# SCH_MCU-IR_Temp-Control-Relay_2025-03-15.net
KiCad netlist of a schematic drawn in EasyEDA
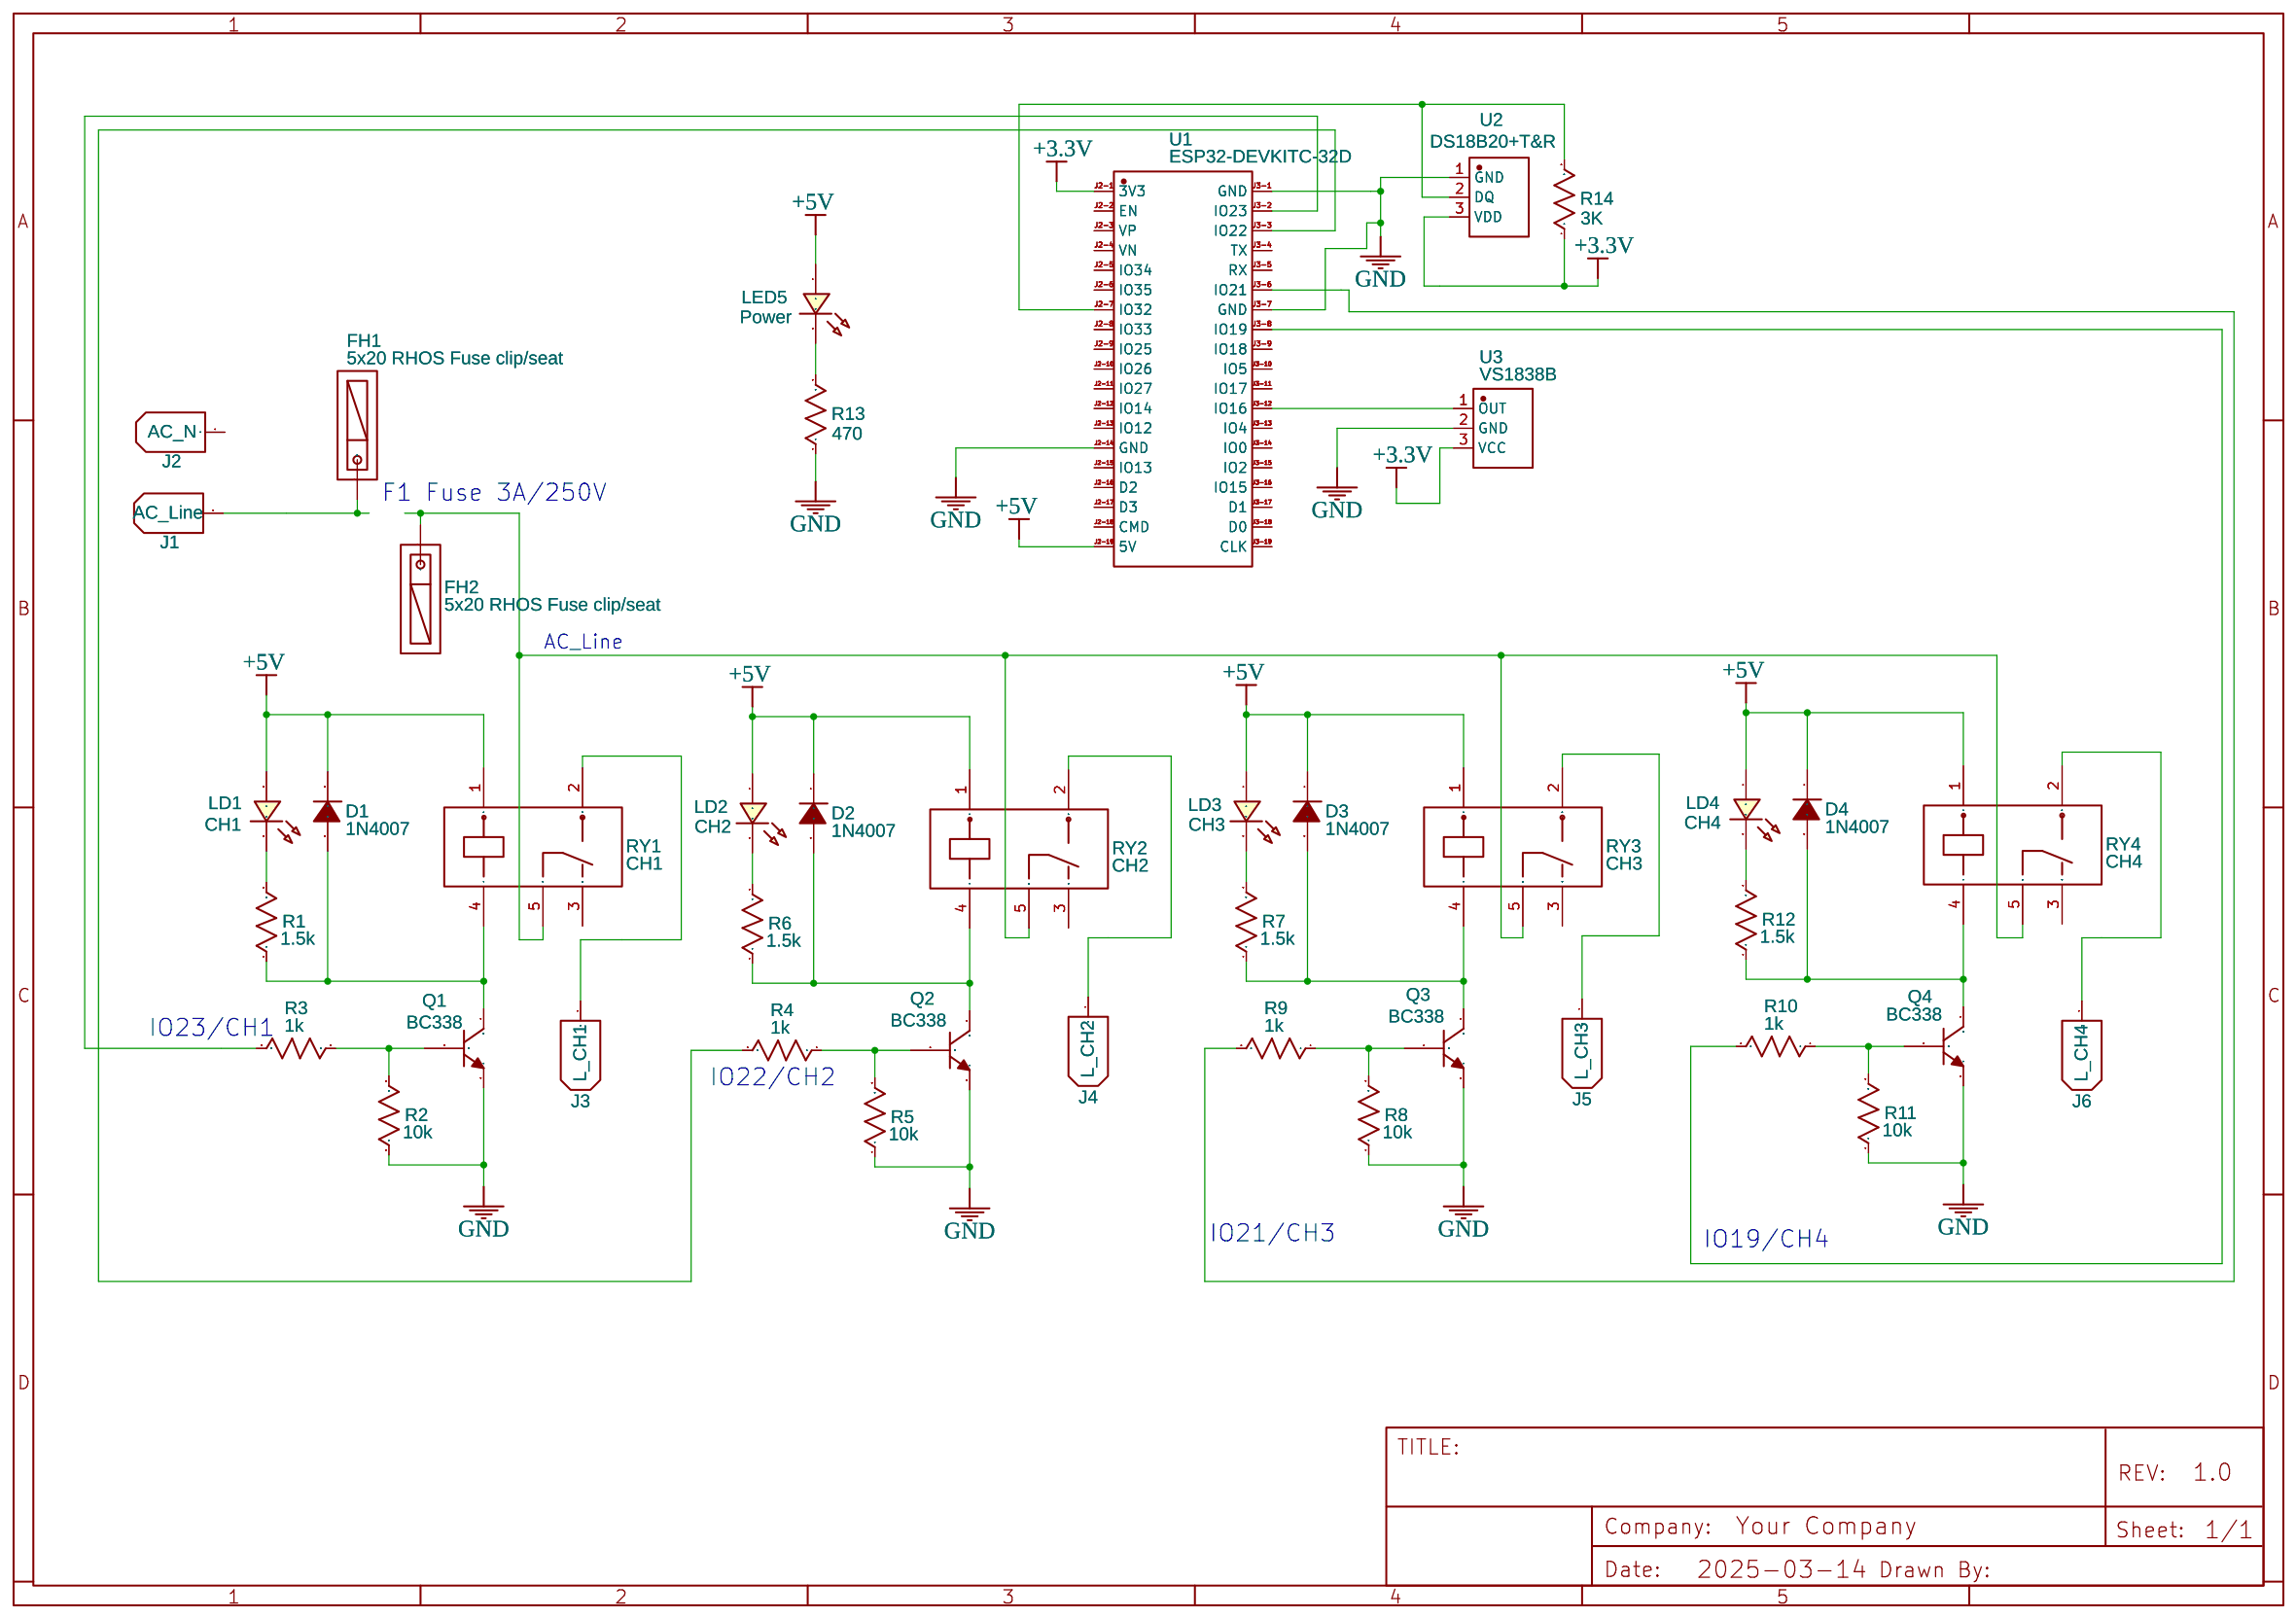
[diagram p0: schematic sheet]

(export (version "E")
  (design (tool "Eeschema 10.0.6"))
  (components
    (comp (ref "D1")
      (value "1N4007")
      (fields (field (name "Manufacturer") "ST(先科)"))
      (libsource (lib "") (part "1N4007"))
    )
    (comp (ref "D2")
      (value "1N4007")
      (fields (field (name "Manufacturer") "ST(先科)"))
      (libsource (lib "") (part "1N4007"))
    )
    (comp (ref "D3")
      (value "1N4007")
      (fields (field (name "Manufacturer") "ST(先科)"))
      (libsource (lib "") (part "1N4007"))
    )
    (comp (ref "D4")
      (value "1N4007")
      (fields (field (name "Manufacturer") "ST(先科)"))
      (libsource (lib "") (part "1N4007"))
    )
    (comp (ref "FH1")
      (value "5x20 RHOS Fuse clip/seat")
      (fields (field (name "Manufacturer Part") "5x20 环保 保险管夹/座") (field (name "Manufacturer") "xcfuse(旭程)"))
      (libsource (lib "") (part "5x20 RHOS Fuse clip/seat"))
    )
    (comp (ref "FH2")
      (value "5x20 RHOS Fuse clip/seat")
      (fields (field (name "Manufacturer Part") "5x20 环保 保险管夹/座") (field (name "Manufacturer") "xcfuse(旭程)"))
      (libsource (lib "") (part "5x20 RHOS Fuse clip/seat_1"))
    )
    (comp (ref "J1")
      (value "AC_Line")
      (fields
        (field (name "Manufacturer Part") "63849-1")
        (field (name "Manufacturer") "TE Connectivity(美国泰科)")
      )
      (libsource (lib "") (part "63849-1_1"))
    )
    (comp (ref "J2")
      (value "AC_N")
      (fields
        (field (name "Manufacturer Part") "63849-1")
        (field (name "Manufacturer") "TE Connectivity(美国泰科)")
      )
      (libsource (lib "") (part "63849-1_1"))
    )
    (comp (ref "J3")
      (value "L_CH1")
      (fields
        (field (name "Manufacturer Part") "63849-1")
        (field (name "Manufacturer") "TE Connectivity(美国泰科)")
      )
      (libsource (lib "") (part "63849-1"))
    )
    (comp (ref "J4")
      (value "L_CH2")
      (fields
        (field (name "Manufacturer Part") "63849-1")
        (field (name "Manufacturer") "TE Connectivity(美国泰科)")
      )
      (libsource (lib "") (part "63849-1"))
    )
    (comp (ref "J5")
      (value "L_CH3")
      (fields
        (field (name "Manufacturer Part") "63849-1")
        (field (name "Manufacturer") "TE Connectivity(美国泰科)")
      )
      (libsource (lib "") (part "63849-1"))
    )
    (comp (ref "J6")
      (value "L_CH4")
      (fields
        (field (name "Manufacturer Part") "63849-1")
        (field (name "Manufacturer") "TE Connectivity(美国泰科)")
      )
      (libsource (lib "") (part "63849-1"))
    )
    (comp (ref "LD1")
      (value "CH1")
      (fields
        (field (name "Manufacturer Part") "204-10SDRD/S530-A3-L")
        (field (name "Manufacturer") "EVERLIGHT(台湾亿光)")
      )
      (libsource (lib "") (part "LED-TH-3mm_R"))
    )
    (comp (ref "LD2")
      (value "CH2")
      (fields
        (field (name "Manufacturer Part") "204-10SDRD/S530-A3-L")
        (field (name "Manufacturer") "EVERLIGHT(台湾亿光)")
      )
      (libsource (lib "") (part "LED-TH-3mm_R"))
    )
    (comp (ref "LD3")
      (value "CH3")
      (fields
        (field (name "Manufacturer Part") "204-10SDRD/S530-A3-L")
        (field (name "Manufacturer") "EVERLIGHT(台湾亿光)")
      )
      (libsource (lib "") (part "LED-TH-3mm_R"))
    )
    (comp (ref "LD4")
      (value "CH4")
      (fields
        (field (name "Manufacturer Part") "204-10SDRD/S530-A3-L")
        (field (name "Manufacturer") "EVERLIGHT(台湾亿光)")
      )
      (libsource (lib "") (part "LED-TH-3mm_R"))
    )
    (comp (ref "LED5")
      (value "Power")
      (fields
        (field (name "Manufacturer Part") "204-10SDRD/S530-A3-L")
        (field (name "Manufacturer") "EVERLIGHT(台湾亿光)")
      )
      (libsource (lib "") (part "LED-TH-3mm_R_1"))
    )
    (comp (ref "Q1")
      (value "BC338")
      (fields (field (name "Manufacturer Part") "BC547BTF") (field (name "Manufacturer") "onsemi(安森美)"))
      (libsource (lib "") (part "BC547BTF"))
    )
    (comp (ref "Q2")
      (value "BC338")
      (fields (field (name "Manufacturer Part") "BC547BTF") (field (name "Manufacturer") "onsemi(安森美)"))
      (libsource (lib "") (part "BC547BTF"))
    )
    (comp (ref "Q3")
      (value "BC338")
      (fields (field (name "Manufacturer Part") "BC547BTF") (field (name "Manufacturer") "onsemi(安森美)"))
      (libsource (lib "") (part "BC547BTF"))
    )
    (comp (ref "Q4")
      (value "BC338")
      (fields (field (name "Manufacturer Part") "BC547BTF") (field (name "Manufacturer") "onsemi(安森美)"))
      (libsource (lib "") (part "BC547BTF"))
    )
    (comp (ref "R1") (value "1.5k") (libsource (lib "") (part "R_AXIAL-0.3_US")))
    (comp (ref "R2") (value "10k") (libsource (lib "") (part "R_AXIAL-0.3_US")))
    (comp (ref "R3") (value "1k") (libsource (lib "") (part "R_AXIAL-0.3_US_1")))
    (comp (ref "R4") (value "1k") (libsource (lib "") (part "R_AXIAL-0.3_US_1")))
    (comp (ref "R5") (value "10k") (libsource (lib "") (part "R_AXIAL-0.3_US")))
    (comp (ref "R6") (value "1.5k") (libsource (lib "") (part "R_AXIAL-0.3_US")))
    (comp (ref "R7") (value "1.5k") (libsource (lib "") (part "R_AXIAL-0.3_US")))
    (comp (ref "R8") (value "10k") (libsource (lib "") (part "R_AXIAL-0.3_US")))
    (comp (ref "R9") (value "1k") (libsource (lib "") (part "R_AXIAL-0.3_US_1")))
    (comp (ref "R10") (value "1k") (libsource (lib "") (part "R_AXIAL-0.3_US_1")))
    (comp (ref "R11") (value "10k") (libsource (lib "") (part "R_AXIAL-0.3_US")))
    (comp (ref "R12") (value "1.5k") (libsource (lib "") (part "R_AXIAL-0.3_US")))
    (comp (ref "R13") (value "470") (libsource (lib "") (part "R_AXIAL-0.3_US")))
    (comp (ref "R14") (value "3K") (libsource (lib "") (part "R_AXIAL-0.3_US")))
    (comp (ref "RY1")
      (value "CH1")
      (fields (field (name "Manufacturer Part") "SRD-12VDC-SL-C") (field (name "Manufacturer") "松乐"))
      (libsource (lib "") (part "SRD-12VDC-SL-C"))
    )
    (comp (ref "RY2")
      (value "CH2")
      (fields (field (name "Manufacturer Part") "SRD-12VDC-SL-C") (field (name "Manufacturer") "松乐"))
      (libsource (lib "") (part "SRD-12VDC-SL-C"))
    )
    (comp (ref "RY3")
      (value "CH3")
      (fields (field (name "Manufacturer Part") "SRD-12VDC-SL-C") (field (name "Manufacturer") "松乐"))
      (libsource (lib "") (part "SRD-12VDC-SL-C"))
    )
    (comp (ref "RY4")
      (value "CH4")
      (fields (field (name "Manufacturer Part") "SRD-12VDC-SL-C") (field (name "Manufacturer") "松乐"))
      (libsource (lib "") (part "SRD-12VDC-SL-C"))
    )
    (comp (ref "U1")
      (value "ESP32-DEVKITC-32D")
      (fields
        (field (name "Manufacturer Part") "ESP32-DevKitC-32D")
        (field (name "Manufacturer") "ESPRESSIF(乐鑫)")
      )
      (libsource (lib "") (part "ESP32-DEVKITC-32D"))
    )
    (comp (ref "U2")
      (value "DS18B20+T&R")
      (fields (field (name "Manufacturer") "ADI(亚德诺)/MAXIM(美信)"))
      (libsource (lib "") (part "DS18B20+T&amp;R"))
    )
    (comp (ref "U3") (value "VS1838B") (libsource (lib "") (part "VS1838B")))
  )
  (nets
    (net (code "1") (name "+3.3V") (class "Default")
      (node (ref "R14") (pin "1") (pinfunction "1_1") (pintype "unspecified"))
      (node (ref "U1") (pin "J2-1") (pinfunction "3V3_J2-1") (pintype "unspecified"))
      (node (ref "U2") (pin "3") (pinfunction "VDD_3") (pintype "unspecified"))
      (node (ref "U3") (pin "3") (pinfunction "VCC_3") (pintype "unspecified"))
    )
    (net (code "2") (name "+5V") (class "Default")
      (node (ref "D1") (pin "1") (pinfunction "K_1") (pintype "unspecified"))
      (node (ref "D2") (pin "1") (pinfunction "K_1") (pintype "unspecified"))
      (node (ref "D3") (pin "1") (pinfunction "K_1") (pintype "unspecified"))
      (node (ref "D4") (pin "1") (pinfunction "K_1") (pintype "unspecified"))
      (node (ref "LD1") (pin "1") (pinfunction "1_1") (pintype "unspecified"))
      (node (ref "LD2") (pin "1") (pinfunction "1_1") (pintype "unspecified"))
      (node (ref "LD3") (pin "1") (pinfunction "1_1") (pintype "unspecified"))
      (node (ref "LD4") (pin "1") (pinfunction "1_1") (pintype "unspecified"))
      (node (ref "LED5") (pin "1") (pinfunction "1_1") (pintype "unspecified"))
      (node (ref "RY1") (pin "1") (pinfunction "1_1") (pintype "input"))
      (node (ref "RY2") (pin "1") (pinfunction "1_1") (pintype "input"))
      (node (ref "RY3") (pin "1") (pinfunction "1_1") (pintype "input"))
      (node (ref "RY4") (pin "1") (pinfunction "1_1") (pintype "input"))
      (node (ref "U1") (pin "J2-19") (pinfunction "5V_J2-19") (pintype "unspecified"))
    )
    (net (code "3") (name "GND") (class "Default")
      (node (ref "Q1") (pin "3") (pinfunction "E_3") (pintype "unspecified"))
      (node (ref "Q2") (pin "3") (pinfunction "E_3") (pintype "unspecified"))
      (node (ref "Q3") (pin "3") (pinfunction "E_3") (pintype "unspecified"))
      (node (ref "Q4") (pin "3") (pinfunction "E_3") (pintype "unspecified"))
      (node (ref "R11") (pin "1") (pinfunction "1_1") (pintype "unspecified"))
      (node (ref "R13") (pin "1") (pinfunction "1_1") (pintype "unspecified"))
      (node (ref "R2") (pin "1") (pinfunction "1_1") (pintype "unspecified"))
      (node (ref "R5") (pin "1") (pinfunction "1_1") (pintype "unspecified"))
      (node (ref "R8") (pin "1") (pinfunction "1_1") (pintype "unspecified"))
      (node (ref "U1") (pin "J2-14") (pinfunction "GND_J2-14") (pintype "unspecified"))
      (node (ref "U1") (pin "J3-1") (pinfunction "GND_J3-1") (pintype "unspecified"))
      (node (ref "U1") (pin "J3-7") (pinfunction "GND_J3-7") (pintype "unspecified"))
      (node (ref "U2") (pin "1") (pinfunction "GND_1") (pintype "unspecified"))
      (node (ref "U3") (pin "2") (pinfunction "GND_2") (pintype "unspecified"))
    )
    (net (code "4") (name "Net-(D1-A)") (class "Default")
      (node (ref "D1") (pin "2") (pinfunction "A_2") (pintype "unspecified"))
      (node (ref "Q1") (pin "1") (pinfunction "C_1") (pintype "unspecified"))
      (node (ref "R1") (pin "1") (pinfunction "1_1") (pintype "unspecified"))
      (node (ref "RY1") (pin "4") (pinfunction "4_4") (pintype "input"))
    )
    (net (code "5") (name "Net-(D2-A)") (class "Default")
      (node (ref "D2") (pin "2") (pinfunction "A_2") (pintype "unspecified"))
      (node (ref "Q2") (pin "1") (pinfunction "C_1") (pintype "unspecified"))
      (node (ref "R6") (pin "1") (pinfunction "1_1") (pintype "unspecified"))
      (node (ref "RY2") (pin "4") (pinfunction "4_4") (pintype "input"))
    )
    (net (code "6") (name "Net-(D3-A)") (class "Default")
      (node (ref "D3") (pin "2") (pinfunction "A_2") (pintype "unspecified"))
      (node (ref "Q3") (pin "1") (pinfunction "C_1") (pintype "unspecified"))
      (node (ref "R7") (pin "1") (pinfunction "1_1") (pintype "unspecified"))
      (node (ref "RY3") (pin "4") (pinfunction "4_4") (pintype "input"))
    )
    (net (code "7") (name "Net-(D4-A)") (class "Default")
      (node (ref "D4") (pin "2") (pinfunction "A_2") (pintype "unspecified"))
      (node (ref "Q4") (pin "1") (pinfunction "C_1") (pintype "unspecified"))
      (node (ref "R12") (pin "1") (pinfunction "1_1") (pintype "unspecified"))
      (node (ref "RY4") (pin "4") (pinfunction "4_4") (pintype "input"))
    )
    (net (code "8") (name "Net-(FH1-Pad1)") (class "Default")
      (node (ref "FH1") (pin "1") (pinfunction "1_1") (pintype "unspecified"))
      (node (ref "J1") (pin "1") (pinfunction "1_1") (pintype "unspecified"))
    )
    (net (code "9") (name "Net-(FH2-Pad1)") (class "Default")
      (node (ref "FH2") (pin "1") (pinfunction "1_1") (pintype "unspecified"))
      (node (ref "RY1") (pin "5") (pinfunction "5_5") (pintype "input"))
      (node (ref "RY2") (pin "5") (pinfunction "5_5") (pintype "input"))
      (node (ref "RY3") (pin "5") (pinfunction "5_5") (pintype "input"))
      (node (ref "RY4") (pin "5") (pinfunction "5_5") (pintype "input"))
    )
    (net (code "10") (name "Net-(J3-Pad1)") (class "Default")
      (node (ref "J3") (pin "1") (pinfunction "1_1") (pintype "unspecified"))
      (node (ref "RY1") (pin "2") (pinfunction "2_2") (pintype "input"))
    )
    (net (code "11") (name "Net-(J4-Pad1)") (class "Default")
      (node (ref "J4") (pin "1") (pinfunction "1_1") (pintype "unspecified"))
      (node (ref "RY2") (pin "2") (pinfunction "2_2") (pintype "input"))
    )
    (net (code "12") (name "Net-(J5-Pad1)") (class "Default")
      (node (ref "J5") (pin "1") (pinfunction "1_1") (pintype "unspecified"))
      (node (ref "RY3") (pin "2") (pinfunction "2_2") (pintype "input"))
    )
    (net (code "13") (name "Net-(J6-Pad1)") (class "Default")
      (node (ref "J6") (pin "1") (pinfunction "1_1") (pintype "unspecified"))
      (node (ref "RY4") (pin "2") (pinfunction "2_2") (pintype "input"))
    )
    (net (code "14") (name "Net-(LD1-Pad2)") (class "Default")
      (node (ref "LD1") (pin "2") (pinfunction "2_2") (pintype "unspecified"))
      (node (ref "R1") (pin "2") (pinfunction "2_2") (pintype "unspecified"))
    )
    (net (code "15") (name "Net-(LD2-Pad2)") (class "Default")
      (node (ref "LD2") (pin "2") (pinfunction "2_2") (pintype "unspecified"))
      (node (ref "R6") (pin "2") (pinfunction "2_2") (pintype "unspecified"))
    )
    (net (code "16") (name "Net-(LD3-Pad2)") (class "Default")
      (node (ref "LD3") (pin "2") (pinfunction "2_2") (pintype "unspecified"))
      (node (ref "R7") (pin "2") (pinfunction "2_2") (pintype "unspecified"))
    )
    (net (code "17") (name "Net-(LD4-Pad2)") (class "Default")
      (node (ref "LD4") (pin "2") (pinfunction "2_2") (pintype "unspecified"))
      (node (ref "R12") (pin "2") (pinfunction "2_2") (pintype "unspecified"))
    )
    (net (code "18") (name "Net-(LED5-Pad2)") (class "Default")
      (node (ref "LED5") (pin "2") (pinfunction "2_2") (pintype "unspecified"))
      (node (ref "R13") (pin "2") (pinfunction "2_2") (pintype "unspecified"))
    )
    (net (code "19") (name "Net-(Q1-B)") (class "Default")
      (node (ref "Q1") (pin "2") (pinfunction "B_2") (pintype "unspecified"))
      (node (ref "R2") (pin "2") (pinfunction "2_2") (pintype "unspecified"))
      (node (ref "R3") (pin "1") (pinfunction "1_1") (pintype "unspecified"))
    )
    (net (code "20") (name "Net-(Q2-B)") (class "Default")
      (node (ref "Q2") (pin "2") (pinfunction "B_2") (pintype "unspecified"))
      (node (ref "R4") (pin "1") (pinfunction "1_1") (pintype "unspecified"))
      (node (ref "R5") (pin "2") (pinfunction "2_2") (pintype "unspecified"))
    )
    (net (code "21") (name "Net-(Q3-B)") (class "Default")
      (node (ref "Q3") (pin "2") (pinfunction "B_2") (pintype "unspecified"))
      (node (ref "R8") (pin "2") (pinfunction "2_2") (pintype "unspecified"))
      (node (ref "R9") (pin "1") (pinfunction "1_1") (pintype "unspecified"))
    )
    (net (code "22") (name "Net-(Q4-B)") (class "Default")
      (node (ref "Q4") (pin "2") (pinfunction "B_2") (pintype "unspecified"))
      (node (ref "R10") (pin "1") (pinfunction "1_1") (pintype "unspecified"))
      (node (ref "R11") (pin "2") (pinfunction "2_2") (pintype "unspecified"))
    )
    (net (code "23") (name "Net-(U1-IO16)") (class "Default")
      (node (ref "U1") (pin "J3-12") (pinfunction "IO16_J3-12") (pintype "unspecified"))
      (node (ref "U3") (pin "1") (pinfunction "OUT_1") (pintype "unspecified"))
    )
    (net (code "24") (name "Net-(U1-IO19)") (class "Default")
      (node (ref "R10") (pin "2") (pinfunction "2_2") (pintype "unspecified"))
      (node (ref "U1") (pin "J3-8") (pinfunction "IO19_J3-8") (pintype "unspecified"))
    )
    (net (code "25") (name "Net-(U1-IO21)") (class "Default")
      (node (ref "R9") (pin "2") (pinfunction "2_2") (pintype "unspecified"))
      (node (ref "U1") (pin "J3-6") (pinfunction "IO21_J3-6") (pintype "unspecified"))
    )
    (net (code "26") (name "Net-(U1-IO22)") (class "Default")
      (node (ref "R4") (pin "2") (pinfunction "2_2") (pintype "unspecified"))
      (node (ref "U1") (pin "J3-3") (pinfunction "IO22_J3-3") (pintype "unspecified"))
    )
    (net (code "27") (name "Net-(U1-IO23)") (class "Default")
      (node (ref "R3") (pin "2") (pinfunction "2_2") (pintype "unspecified"))
      (node (ref "U1") (pin "J3-2") (pinfunction "IO23_J3-2") (pintype "unspecified"))
    )
    (net (code "28") (name "Net-(U1-IO32)") (class "Default")
      (node (ref "R14") (pin "2") (pinfunction "2_2") (pintype "unspecified"))
      (node (ref "U1") (pin "J2-7") (pinfunction "IO32_J2-7") (pintype "unspecified"))
      (node (ref "U2") (pin "2") (pinfunction "DQ_2") (pintype "unspecified"))
    )
    (net (code "29") (name "unconnected-(J2-Pad1)") (class "Default")
      (node (ref "J2") (pin "1") (pinfunction "1_1") (pintype "unspecified"))
    )
    (net (code "30") (name "unconnected-(RY1-Pad3)") (class "Default")
      (node (ref "RY1") (pin "3") (pinfunction "3_3") (pintype "input"))
    )
    (net (code "31") (name "unconnected-(RY2-Pad3)") (class "Default")
      (node (ref "RY2") (pin "3") (pinfunction "3_3") (pintype "input"))
    )
    (net (code "32") (name "unconnected-(RY3-Pad3)") (class "Default")
      (node (ref "RY3") (pin "3") (pinfunction "3_3") (pintype "input"))
    )
    (net (code "33") (name "unconnected-(RY4-Pad3)") (class "Default")
      (node (ref "RY4") (pin "3") (pinfunction "3_3") (pintype "input"))
    )
    (net (code "34") (name "unconnected-(U1-CLK-PadJ3-19)") (class "Default")
      (node (ref "U1") (pin "J3-19") (pinfunction "CLK_J3-19") (pintype "unspecified"))
    )
    (net (code "35") (name "unconnected-(U1-CMD-PadJ2-18)") (class "Default")
      (node (ref "U1") (pin "J2-18") (pinfunction "CMD_J2-18") (pintype "unspecified"))
    )
    (net (code "36") (name "unconnected-(U1-D0-PadJ3-18)") (class "Default")
      (node (ref "U1") (pin "J3-18") (pinfunction "D0_J3-18") (pintype "unspecified"))
    )
    (net (code "37") (name "unconnected-(U1-D1-PadJ3-17)") (class "Default")
      (node (ref "U1") (pin "J3-17") (pinfunction "D1_J3-17") (pintype "unspecified"))
    )
    (net (code "38") (name "unconnected-(U1-D2-PadJ2-16)") (class "Default")
      (node (ref "U1") (pin "J2-16") (pinfunction "D2_J2-16") (pintype "unspecified"))
    )
    (net (code "39") (name "unconnected-(U1-D3-PadJ2-17)") (class "Default")
      (node (ref "U1") (pin "J2-17") (pinfunction "D3_J2-17") (pintype "unspecified"))
    )
    (net (code "40") (name "unconnected-(U1-EN-PadJ2-2)") (class "Default")
      (node (ref "U1") (pin "J2-2") (pinfunction "EN_J2-2") (pintype "unspecified"))
    )
    (net (code "41") (name "unconnected-(U1-IO0-PadJ3-14)") (class "Default")
      (node (ref "U1") (pin "J3-14") (pinfunction "IO0_J3-14") (pintype "unspecified"))
    )
    (net (code "42") (name "unconnected-(U1-IO2-PadJ3-15)") (class "Default")
      (node (ref "U1") (pin "J3-15") (pinfunction "IO2_J3-15") (pintype "unspecified"))
    )
    (net (code "43") (name "unconnected-(U1-IO4-PadJ3-13)") (class "Default")
      (node (ref "U1") (pin "J3-13") (pinfunction "IO4_J3-13") (pintype "unspecified"))
    )
    (net (code "44") (name "unconnected-(U1-IO5-PadJ3-10)") (class "Default")
      (node (ref "U1") (pin "J3-10") (pinfunction "IO5_J3-10") (pintype "unspecified"))
    )
    (net (code "45") (name "unconnected-(U1-IO12-PadJ2-13)") (class "Default")
      (node (ref "U1") (pin "J2-13") (pinfunction "IO12_J2-13") (pintype "unspecified"))
    )
    (net (code "46") (name "unconnected-(U1-IO13-PadJ2-15)") (class "Default")
      (node (ref "U1") (pin "J2-15") (pinfunction "IO13_J2-15") (pintype "unspecified"))
    )
    (net (code "47") (name "unconnected-(U1-IO14-PadJ2-12)") (class "Default")
      (node (ref "U1") (pin "J2-12") (pinfunction "IO14_J2-12") (pintype "unspecified"))
    )
    (net (code "48") (name "unconnected-(U1-IO15-PadJ3-16)") (class "Default")
      (node (ref "U1") (pin "J3-16") (pinfunction "IO15_J3-16") (pintype "unspecified"))
    )
    (net (code "49") (name "unconnected-(U1-IO17-PadJ3-11)") (class "Default")
      (node (ref "U1") (pin "J3-11") (pinfunction "IO17_J3-11") (pintype "unspecified"))
    )
    (net (code "50") (name "unconnected-(U1-IO18-PadJ3-9)") (class "Default")
      (node (ref "U1") (pin "J3-9") (pinfunction "IO18_J3-9") (pintype "unspecified"))
    )
    (net (code "51") (name "unconnected-(U1-IO25-PadJ2-9)") (class "Default")
      (node (ref "U1") (pin "J2-9") (pinfunction "IO25_J2-9") (pintype "unspecified"))
    )
    (net (code "52") (name "unconnected-(U1-IO26-PadJ2-10)") (class "Default")
      (node (ref "U1") (pin "J2-10") (pinfunction "IO26_J2-10") (pintype "unspecified"))
    )
    (net (code "53") (name "unconnected-(U1-IO27-PadJ2-11)") (class "Default")
      (node (ref "U1") (pin "J2-11") (pinfunction "IO27_J2-11") (pintype "unspecified"))
    )
    (net (code "54") (name "unconnected-(U1-IO33-PadJ2-8)") (class "Default")
      (node (ref "U1") (pin "J2-8") (pinfunction "IO33_J2-8") (pintype "unspecified"))
    )
    (net (code "55") (name "unconnected-(U1-IO34-PadJ2-5)") (class "Default")
      (node (ref "U1") (pin "J2-5") (pinfunction "IO34_J2-5") (pintype "unspecified"))
    )
    (net (code "56") (name "unconnected-(U1-IO35-PadJ2-6)") (class "Default")
      (node (ref "U1") (pin "J2-6") (pinfunction "IO35_J2-6") (pintype "unspecified"))
    )
    (net (code "57") (name "unconnected-(U1-RX-PadJ3-5)") (class "Default")
      (node (ref "U1") (pin "J3-5") (pinfunction "RX_J3-5") (pintype "unspecified"))
    )
    (net (code "58") (name "unconnected-(U1-TX-PadJ3-4)") (class "Default")
      (node (ref "U1") (pin "J3-4") (pinfunction "TX_J3-4") (pintype "unspecified"))
    )
    (net (code "59") (name "unconnected-(U1-VN-PadJ2-4)") (class "Default")
      (node (ref "U1") (pin "J2-4") (pinfunction "VN_J2-4") (pintype "unspecified"))
    )
    (net (code "60") (name "unconnected-(U1-VP-PadJ2-3)") (class "Default")
      (node (ref "U1") (pin "J2-3") (pinfunction "VP_J2-3") (pintype "unspecified"))
    )
  )
)
